# ExenMiniShield.net
KiCad netlist of a schematic drawn in EAGLE
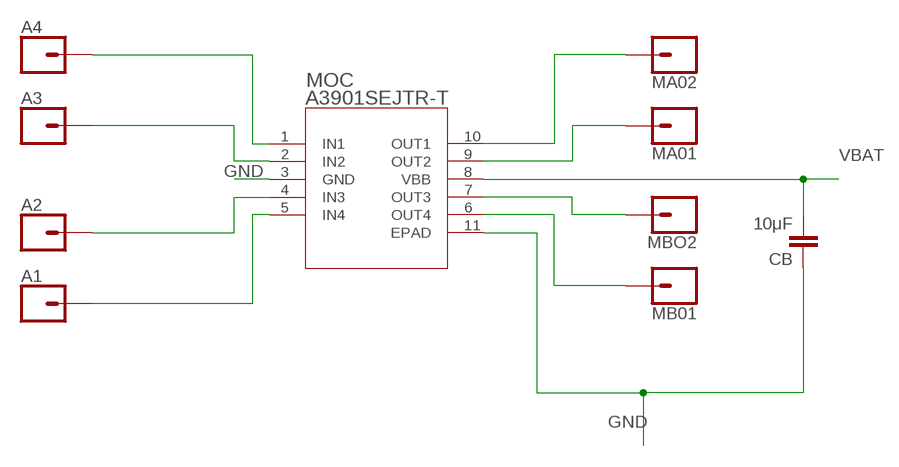
[diagram p0: schematic, sheet 1]
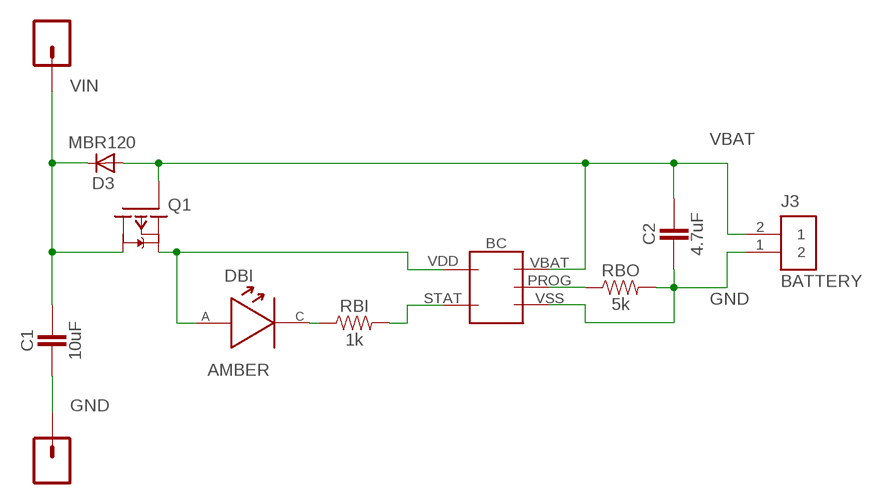
[diagram p1: schematic, sheet 2]
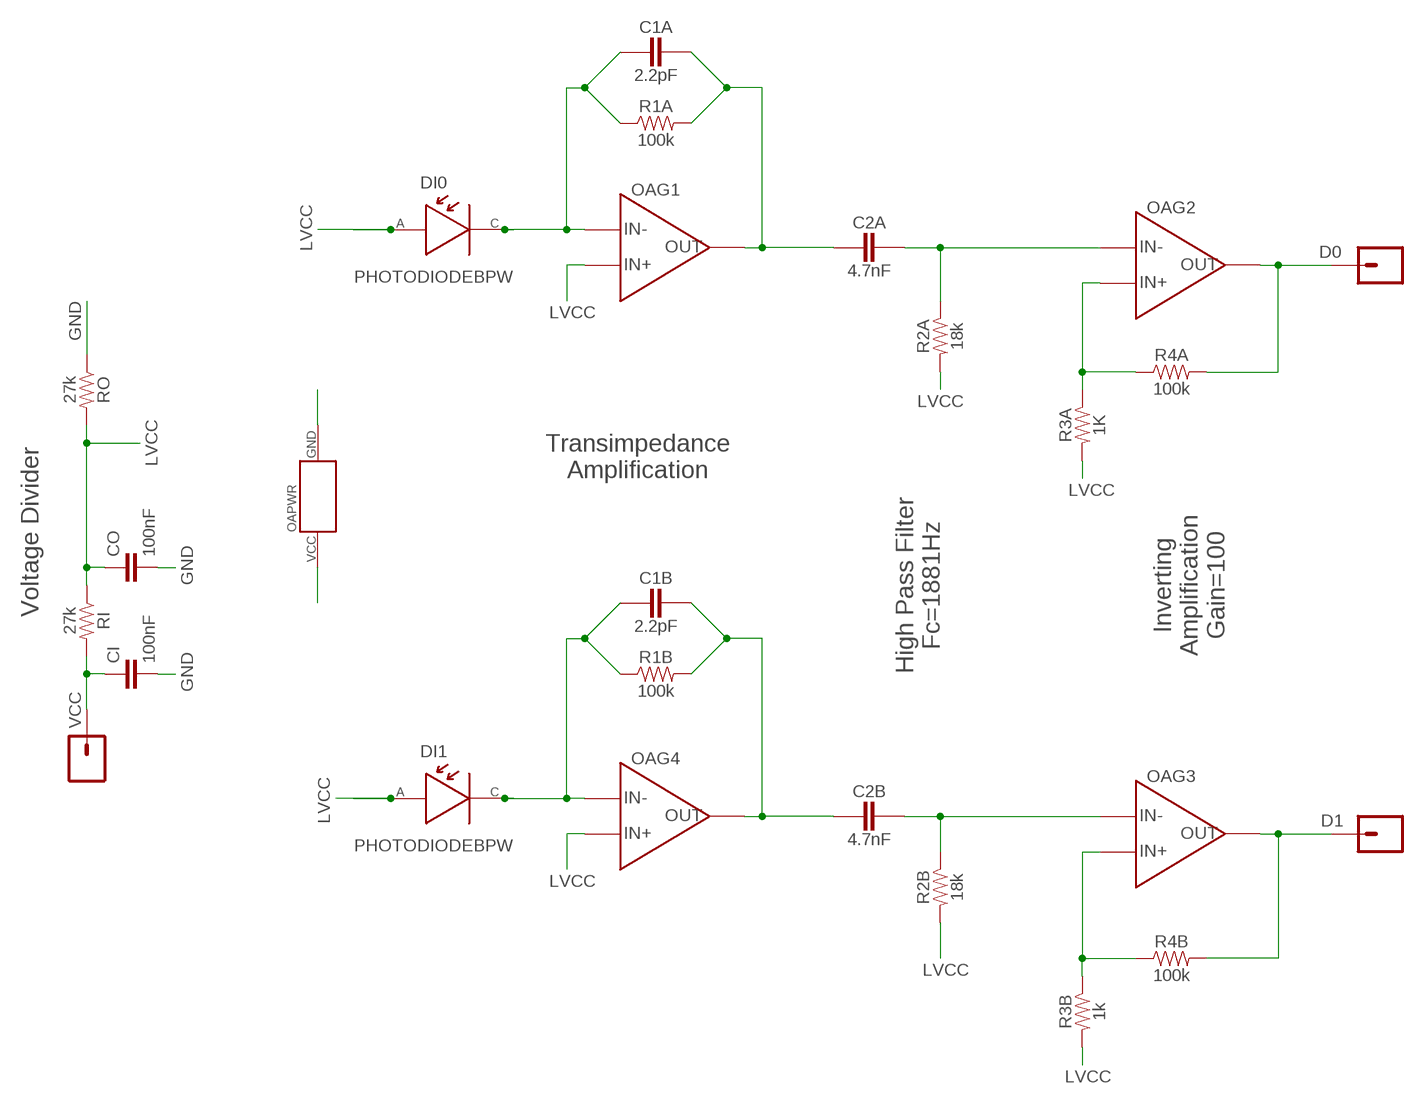
[diagram p2: schematic, sheet 3]

(export (version "E")
  (design (tool "Eeschema 10.0.6"))
  (components
    (comp (ref "C1A")
      (value "2.2pF")
      (footprint "eagle-import:PASSIVE-0603")
      (libsource (lib "eagle-import") (part "CAPACITOR"))
    )
    (comp (ref "C1B")
      (value "2.2pF")
      (footprint "eagle-import:PASSIVE-0603")
      (libsource (lib "eagle-import") (part "CAPACITOR"))
    )
    (comp (ref "C2A")
      (value "4.7nF")
      (footprint "eagle-import:PASSIVE-0603")
      (libsource (lib "eagle-import") (part "CAPACITOR"))
    )
    (comp (ref "C2B")
      (value "4.7nF")
      (footprint "eagle-import:PASSIVE-0603")
      (libsource (lib "eagle-import") (part "CAPACITOR"))
    )
    (comp (ref "CI")
      (value "100nF")
      (footprint "eagle-import:0603")
      (libsource (lib "eagle-import") (part "4.7PF-0603-50V-5%"))
    )
    (comp (ref "CO")
      (value "100nF")
      (footprint "eagle-import:0603")
      (libsource (lib "eagle-import") (part "4.7PF-0603-50V-5%"))
    )
    (comp (ref "D0")
      (value "CONN_01PTH_NO_SILK_YES_STOP")
      (footprint "eagle-import:1X01_NO_SILK")
      (libsource (lib "eagle-import") (part "CONN_01PTH_NO_SILK_YES_STOP"))
    )
    (comp (ref "D1")
      (value "CONN_01PTH_NO_SILK_YES_STOP")
      (footprint "eagle-import:1X01_NO_SILK")
      (libsource (lib "eagle-import") (part "CONN_01PTH_NO_SILK_YES_STOP"))
    )
    (comp (ref "DI0")
      (value "PHOTODIODEBPW")
      (footprint "eagle-import:BPW34_BP104_SMD")
      (libsource (lib "eagle-import") (part "PHOTODIODEBPW"))
    )
    (comp (ref "DI1")
      (value "PHOTODIODEBPW")
      (footprint "eagle-import:BPW34_BP104_SMD")
      (libsource (lib "eagle-import") (part "PHOTODIODEBPW"))
    )
    (comp (ref "OA")
      (value "TLV2464IPW")
      (footprint "eagle-import:PW14")
      (libsource (lib "eagle-import") (part "TLV2464IPW"))
    )
    (comp (ref "R1A")
      (value "100k")
      (footprint "eagle-import:PASSIVE-0603")
      (libsource (lib "eagle-import") (part "RESISTOR"))
    )
    (comp (ref "R1B")
      (value "100k")
      (footprint "eagle-import:PASSIVE-0603")
      (libsource (lib "eagle-import") (part "RESISTOR"))
    )
    (comp (ref "R2A")
      (value "18k")
      (footprint "eagle-import:PASSIVE-0603")
      (libsource (lib "eagle-import") (part "RESISTOR"))
    )
    (comp (ref "R2B")
      (value "18k")
      (footprint "eagle-import:PASSIVE-0603")
      (libsource (lib "eagle-import") (part "RESISTOR"))
    )
    (comp (ref "R3A")
      (value "1K")
      (footprint "eagle-import:PASSIVE-0603")
      (libsource (lib "eagle-import") (part "RESISTOR"))
    )
    (comp (ref "R3B")
      (value "1k")
      (footprint "eagle-import:PASSIVE-0603")
      (libsource (lib "eagle-import") (part "RESISTOR"))
    )
    (comp (ref "R4A")
      (value "100k")
      (footprint "eagle-import:PASSIVE-0603")
      (libsource (lib "eagle-import") (part "RESISTOR"))
    )
    (comp (ref "R4B")
      (value "100k")
      (footprint "eagle-import:PASSIVE-0603")
      (libsource (lib "eagle-import") (part "RESISTOR"))
    )
    (comp (ref "RI")
      (value "27k")
      (footprint "eagle-import:0603")
      (libsource (lib "eagle-import") (part "100KOHM-0603-1/10W-1%"))
    )
    (comp (ref "RO")
      (value "27k")
      (footprint "eagle-import:0603")
      (libsource (lib "eagle-import") (part "100KOHM-0603-1/10W-1%"))
    )
    (comp (ref "VCC")
      (value "CONN_01PTH_NO_SILK_YES_STOP")
      (footprint "eagle-import:1X01_NO_SILK")
      (libsource (lib "eagle-import") (part "CONN_01PTH_NO_SILK_YES_STOP"))
    )
    (comp (ref "BC")
      (value "BATTERYCHARGER")
      (footprint "eagle-import:SOT-753")
      (libsource (lib "eagle-import") (part "BATTERYCHARGER"))
    )
    (comp (ref "C1")
      (value "10uF")
      (footprint "eagle-import:PASSIVE-0603")
      (libsource (lib "eagle-import") (part "CAPACITOR"))
    )
    (comp (ref "C2")
      (value "4.7uF")
      (footprint "eagle-import:PASSIVE-0603")
      (libsource (lib "eagle-import") (part "CAPACITOR"))
    )
    (comp (ref "D3")
      (value "MBR120")
      (footprint "eagle-import:SOD-123FL")
      (fields (field (name "PARTNO") "AS-ITM-00111"))
      (libsource (lib "eagle-import") (part "AS-ITM-00111"))
    )
    (comp (ref "DBI")
      (value "AMBER")
      (footprint "eagle-import:PASSIVE-0603")
      (libsource (lib "eagle-import") (part "DIODE"))
    )
    (comp (ref "GND")
      (value "CONN_01PTH_NO_SILK_YES_STOP")
      (footprint "eagle-import:1X01_NO_SILK")
      (libsource (lib "eagle-import") (part "CONN_01PTH_NO_SILK_YES_STOP"))
    )
    (comp (ref "J3")
      (value "BATTERY")
      (footprint "eagle-import:JST_SH_2X1")
      (fields (field (name "PARTNO") "AS-ITM-00231"))
      (libsource (lib "eagle-import") (part "AS-ITM-00231"))
    )
    (comp (ref "Q1")
      (value "DMP2035U")
      (footprint "eagle-import:SOT23")
      (fields (field (name "PARTNO") "AS-ITM-00024"))
      (libsource (lib "eagle-import") (part "AS-ITM-00024"))
    )
    (comp (ref "RBI")
      (value "1k")
      (footprint "eagle-import:PASSIVE-0603")
      (libsource (lib "eagle-import") (part "RESISTOR"))
    )
    (comp (ref "RBO")
      (value "5k")
      (footprint "eagle-import:PASSIVE-0603")
      (libsource (lib "eagle-import") (part "RESISTOR"))
    )
    (comp (ref "VIN")
      (value "CONN_01PTH_NO_SILK_YES_STOP")
      (footprint "eagle-import:1X01_NO_SILK")
      (libsource (lib "eagle-import") (part "CONN_01PTH_NO_SILK_YES_STOP"))
    )
    (comp (ref "A1")
      (value "CONN_01PTH_NO_SILK_YES_STOP")
      (footprint "eagle-import:1X01_NO_SILK")
      (libsource (lib "eagle-import") (part "CONN_01PTH_NO_SILK_YES_STOP"))
    )
    (comp (ref "A2")
      (value "CONN_01PTH_NO_SILK_YES_STOP")
      (footprint "eagle-import:1X01_NO_SILK")
      (libsource (lib "eagle-import") (part "CONN_01PTH_NO_SILK_YES_STOP"))
    )
    (comp (ref "A3")
      (value "CONN_01PTH_NO_SILK_YES_STOP")
      (footprint "eagle-import:1X01_NO_SILK")
      (libsource (lib "eagle-import") (part "CONN_01PTH_NO_SILK_YES_STOP"))
    )
    (comp (ref "A4")
      (value "CONN_01PTH_NO_SILK_YES_STOP")
      (footprint "eagle-import:1X01_NO_SILK")
      (libsource (lib "eagle-import") (part "CONN_01PTH_NO_SILK_YES_STOP"))
    )
    (comp (ref "CB")
      (value "10μF")
      (footprint "eagle-import:0603")
      (libsource (lib "eagle-import") (part "4.7PF-0603-50V-5%"))
    )
    (comp (ref "MA01")
      (value "CONN_01PTH_NO_SILK_YES_STOP")
      (footprint "eagle-import:1X01_NO_SILK")
      (libsource (lib "eagle-import") (part "CONN_01PTH_NO_SILK_YES_STOP"))
    )
    (comp (ref "MA02")
      (value "CONN_01PTH_NO_SILK_YES_STOP")
      (footprint "eagle-import:1X01_NO_SILK")
      (libsource (lib "eagle-import") (part "CONN_01PTH_NO_SILK_YES_STOP"))
    )
    (comp (ref "MB01")
      (value "CONN_01PTH_NO_SILK_YES_STOP")
      (footprint "eagle-import:1X01_NO_SILK")
      (libsource (lib "eagle-import") (part "CONN_01PTH_NO_SILK_YES_STOP"))
    )
    (comp (ref "MBO2")
      (value "CONN_01PTH_NO_SILK_YES_STOP")
      (footprint "eagle-import:1X01_NO_SILK")
      (libsource (lib "eagle-import") (part "CONN_01PTH_NO_SILK_YES_STOP"))
    )
    (comp (ref "MOC")
      (value "A3901SEJTR-T")
      (footprint "eagle-import:DFN-10_DD")
      (libsource (lib "eagle-import") (part "A3901SEJTR-T"))
    )
  )
  (nets
    (net (code "1") (name "D0") (class "Default")
      (node (ref "D0") (pin "1") (pinfunction "1_1") (pintype "passive"))
      (node (ref "OA") (pin "7") (pinfunction "OUT_7") (pintype "bidirectional"))
      (node (ref "R4A") (pin "2") (pinfunction "2_2") (pintype "passive"))
    )
    (net (code "2") (name "D1") (class "Default")
      (node (ref "D1") (pin "1") (pinfunction "1_1") (pintype "passive"))
      (node (ref "OA") (pin "8") (pinfunction "OUT_8") (pintype "bidirectional"))
      (node (ref "R4B") (pin "2") (pinfunction "2_2") (pintype "passive"))
    )
    (net (code "3") (name "GND") (class "Default")
      (node (ref "BC") (pin "VSS") (pinfunction "VSS_VSS") (pintype "bidirectional"))
      (node (ref "C1") (pin "1") (pinfunction "1_1") (pintype "passive"))
      (node (ref "C2") (pin "1") (pinfunction "1_1") (pintype "passive"))
      (node (ref "CB") (pin "1") (pinfunction "1_1") (pintype "passive"))
      (node (ref "CI") (pin "2") (pinfunction "2_2") (pintype "passive"))
      (node (ref "CO") (pin "2") (pinfunction "2_2") (pintype "passive"))
      (node (ref "GND") (pin "1") (pinfunction "1_1") (pintype "passive"))
      (node (ref "J3") (pin "1") (pinfunction "2_1") (pintype "bidirectional"))
      (node (ref "MOC") (pin "11") (pinfunction "EPAD_11") (pintype "passive"))
      (node (ref "MOC") (pin "3") (pinfunction "GND_3") (pintype "power_in"))
      (node (ref "OA") (pin "11") (pinfunction "GND_11") (pintype "bidirectional"))
      (node (ref "RBO") (pin "2") (pinfunction "2_2") (pintype "passive"))
      (node (ref "RO") (pin "1") (pinfunction "1_1") (pintype "passive"))
    )
    (net (code "4") (name "LVCC") (class "Default")
      (node (ref "CO") (pin "1") (pinfunction "1_1") (pintype "passive"))
      (node (ref "DI0") (pin "ANODE") (pinfunction "ANODE_ANODE") (pintype "bidirectional"))
      (node (ref "DI1") (pin "ANODE") (pinfunction "ANODE_ANODE") (pintype "bidirectional"))
      (node (ref "OA") (pin "12") (pinfunction "IN+_12") (pintype "bidirectional"))
      (node (ref "OA") (pin "3") (pinfunction "IN+_3") (pintype "bidirectional"))
      (node (ref "R2A") (pin "2") (pinfunction "2_2") (pintype "passive"))
      (node (ref "R2B") (pin "2") (pinfunction "2_2") (pintype "passive"))
      (node (ref "R3A") (pin "2") (pinfunction "2_2") (pintype "passive"))
      (node (ref "R3B") (pin "2") (pinfunction "2_2") (pintype "passive"))
      (node (ref "RI") (pin "1") (pinfunction "1_1") (pintype "passive"))
      (node (ref "RO") (pin "2") (pinfunction "2_2") (pintype "passive"))
    )
    (net (code "5") (name "Net-(BC-PadPROG)") (class "Default")
      (node (ref "BC") (pin "PROG") (pinfunction "PROG_PROG") (pintype "bidirectional"))
      (node (ref "RBO") (pin "1") (pinfunction "1_1") (pintype "passive"))
    )
    (net (code "6") (name "Net-(BC-PadSTAT)") (class "Default")
      (node (ref "BC") (pin "STAT") (pinfunction "STAT_STAT") (pintype "bidirectional"))
      (node (ref "RBI") (pin "2") (pinfunction "2_2") (pintype "passive"))
    )
    (net (code "7") (name "Net-(DBI-ANODE)") (class "Default")
      (node (ref "BC") (pin "VDD") (pinfunction "VDD_VDD") (pintype "bidirectional"))
      (node (ref "DBI") (pin "1") (pinfunction "ANODE_1") (pintype "bidirectional"))
      (node (ref "Q1") (pin "E") (pinfunction "S_E") (pintype "passive"))
    )
    (net (code "8") (name "Net-(DBI-CATHODE)") (class "Default")
      (node (ref "DBI") (pin "2") (pinfunction "CATHODE_2") (pintype "bidirectional"))
      (node (ref "RBI") (pin "1") (pinfunction "1_1") (pintype "passive"))
    )
    (net (code "9") (name "Net-(MOC-IN1)") (class "Default")
      (node (ref "A4") (pin "1") (pinfunction "1_1") (pintype "passive"))
      (node (ref "MOC") (pin "1") (pinfunction "IN1_1") (pintype "passive"))
    )
    (net (code "10") (name "Net-(MOC-IN2)") (class "Default")
      (node (ref "A3") (pin "1") (pinfunction "1_1") (pintype "passive"))
      (node (ref "MOC") (pin "2") (pinfunction "IN2_2") (pintype "passive"))
    )
    (net (code "11") (name "Net-(MOC-IN3)") (class "Default")
      (node (ref "A2") (pin "1") (pinfunction "1_1") (pintype "passive"))
      (node (ref "MOC") (pin "4") (pinfunction "IN3_4") (pintype "passive"))
    )
    (net (code "12") (name "Net-(MOC-IN4)") (class "Default")
      (node (ref "A1") (pin "1") (pinfunction "1_1") (pintype "passive"))
      (node (ref "MOC") (pin "5") (pinfunction "IN4_5") (pintype "passive"))
    )
    (net (code "13") (name "Net-(MOC-OUT1)") (class "Default")
      (node (ref "MA02") (pin "1") (pinfunction "1_1") (pintype "passive"))
      (node (ref "MOC") (pin "10") (pinfunction "OUT1_10") (pintype "output"))
    )
    (net (code "14") (name "Net-(MOC-OUT2)") (class "Default")
      (node (ref "MA01") (pin "1") (pinfunction "1_1") (pintype "passive"))
      (node (ref "MOC") (pin "9") (pinfunction "OUT2_9") (pintype "output"))
    )
    (net (code "15") (name "Net-(MOC-OUT3)") (class "Default")
      (node (ref "MBO2") (pin "1") (pinfunction "1_1") (pintype "passive"))
      (node (ref "MOC") (pin "7") (pinfunction "OUT3_7") (pintype "output"))
    )
    (net (code "16") (name "Net-(MOC-OUT4)") (class "Default")
      (node (ref "MB01") (pin "1") (pinfunction "1_1") (pintype "passive"))
      (node (ref "MOC") (pin "6") (pinfunction "OUT4_6") (pintype "output"))
    )
    (net (code "17") (name "Net-(OAA-IN-)") (class "Default")
      (node (ref "C1A") (pin "1") (pinfunction "1_1") (pintype "passive"))
      (node (ref "DI0") (pin "CATHODE") (pinfunction "CATHODE_CATHODE") (pintype "bidirectional"))
      (node (ref "OA") (pin "2") (pinfunction "IN-_2") (pintype "bidirectional"))
      (node (ref "R1A") (pin "1") (pinfunction "1_1") (pintype "passive"))
    )
    (net (code "18") (name "Net-(OAA-OUT)") (class "Default")
      (node (ref "C1A") (pin "2") (pinfunction "2_2") (pintype "passive"))
      (node (ref "C2A") (pin "1") (pinfunction "1_1") (pintype "passive"))
      (node (ref "OA") (pin "1") (pinfunction "OUT_1") (pintype "bidirectional"))
      (node (ref "R1A") (pin "2") (pinfunction "2_2") (pintype "passive"))
    )
    (net (code "19") (name "Net-(OAB-IN+)") (class "Default")
      (node (ref "OA") (pin "5") (pinfunction "IN+_5") (pintype "bidirectional"))
      (node (ref "R3A") (pin "1") (pinfunction "1_1") (pintype "passive"))
      (node (ref "R4A") (pin "1") (pinfunction "1_1") (pintype "passive"))
    )
    (net (code "20") (name "Net-(OAB-IN-)") (class "Default")
      (node (ref "C2A") (pin "2") (pinfunction "2_2") (pintype "passive"))
      (node (ref "OA") (pin "6") (pinfunction "IN-_6") (pintype "bidirectional"))
      (node (ref "R2A") (pin "1") (pinfunction "1_1") (pintype "passive"))
    )
    (net (code "21") (name "Net-(OAC-IN+)") (class "Default")
      (node (ref "OA") (pin "10") (pinfunction "IN+_10") (pintype "bidirectional"))
      (node (ref "R3B") (pin "1") (pinfunction "1_1") (pintype "passive"))
      (node (ref "R4B") (pin "1") (pinfunction "1_1") (pintype "passive"))
    )
    (net (code "22") (name "Net-(OAC-IN-)") (class "Default")
      (node (ref "C2B") (pin "2") (pinfunction "2_2") (pintype "passive"))
      (node (ref "OA") (pin "9") (pinfunction "IN-_9") (pintype "bidirectional"))
      (node (ref "R2B") (pin "1") (pinfunction "1_1") (pintype "passive"))
    )
    (net (code "23") (name "Net-(OAD-IN-)") (class "Default")
      (node (ref "C1B") (pin "1") (pinfunction "1_1") (pintype "passive"))
      (node (ref "DI1") (pin "CATHODE") (pinfunction "CATHODE_CATHODE") (pintype "bidirectional"))
      (node (ref "OA") (pin "13") (pinfunction "IN-_13") (pintype "bidirectional"))
      (node (ref "R1B") (pin "1") (pinfunction "1_1") (pintype "passive"))
    )
    (net (code "24") (name "Net-(OAD-OUT)") (class "Default")
      (node (ref "C1B") (pin "2") (pinfunction "2_2") (pintype "passive"))
      (node (ref "C2B") (pin "1") (pinfunction "1_1") (pintype "passive"))
      (node (ref "OA") (pin "14") (pinfunction "OUT_14") (pintype "bidirectional"))
      (node (ref "R1B") (pin "2") (pinfunction "2_2") (pintype "passive"))
    )
    (net (code "25") (name "VBAT") (class "Default")
      (node (ref "BC") (pin "VBAT") (pinfunction "VBAT_VBAT") (pintype "bidirectional"))
      (node (ref "C2") (pin "2") (pinfunction "2_2") (pintype "passive"))
      (node (ref "CB") (pin "2") (pinfunction "2_2") (pintype "passive"))
      (node (ref "D3") (pin "A") (pinfunction "A_A") (pintype "passive"))
      (node (ref "J3") (pin "2") (pinfunction "1_2") (pintype "bidirectional"))
      (node (ref "MOC") (pin "8") (pinfunction "VBB_8") (pintype "power_in"))
      (node (ref "Q1") (pin "B") (pinfunction "G_B") (pintype "passive"))
    )
    (net (code "26") (name "VCC") (class "Default")
      (node (ref "CI") (pin "1") (pinfunction "1_1") (pintype "passive"))
      (node (ref "OA") (pin "4") (pinfunction "VCC_4") (pintype "bidirectional"))
      (node (ref "RI") (pin "2") (pinfunction "2_2") (pintype "passive"))
      (node (ref "VCC") (pin "1") (pinfunction "1_1") (pintype "passive"))
    )
    (net (code "27") (name "VIN") (class "Default")
      (node (ref "C1") (pin "2") (pinfunction "2_2") (pintype "passive"))
      (node (ref "D3") (pin "C") (pinfunction "C_C") (pintype "passive"))
      (node (ref "Q1") (pin "C") (pinfunction "D_C") (pintype "passive"))
      (node (ref "VIN") (pin "1") (pinfunction "1_1") (pintype "passive"))
    )
  )
)
